# OurEDA-P1K_Network.net
KiCad netlist of a schematic drawn in Altium Designer
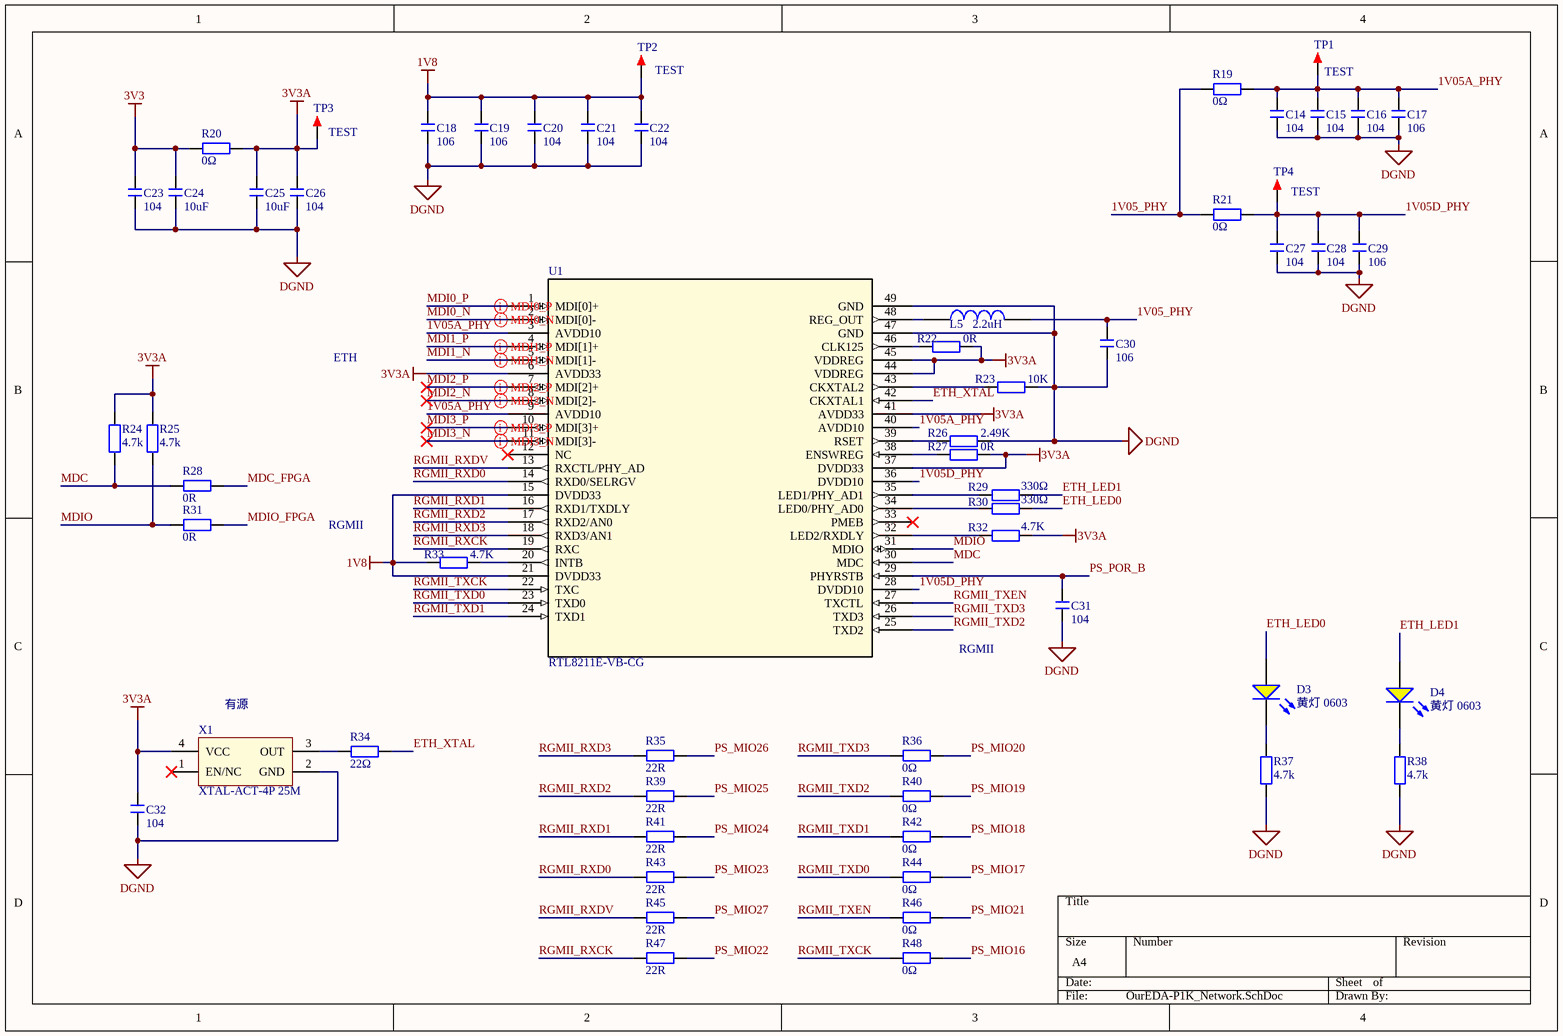
[diagram p0: OurEDA-P1K_Network.SchDoc]

(export (version "E")
  (design (tool "Eeschema 10.0.6"))
  (components
    (comp (ref "C14")
      (value "104")
      (footprint "C 0603_L")
      (description "无极性贴片电容")
      (fields (field (name "版权归属") "源创客"))
      (libsource (lib "3.1   - 电阻-电容-电感") (part "C"))
    )
    (comp (ref "C15")
      (value "104")
      (footprint "C 0603_L")
      (description "无极性贴片电容")
      (fields (field (name "版权归属") "源创客"))
      (libsource (lib "3.1   - 电阻-电容-电感") (part "C"))
    )
    (comp (ref "C16")
      (value "104")
      (footprint "C 0603_L")
      (description "无极性贴片电容")
      (fields (field (name "版权归属") "源创客"))
      (libsource (lib "3.1   - 电阻-电容-电感") (part "C"))
    )
    (comp (ref "C17")
      (value "106")
      (footprint "C 0603_L")
      (description "无极性贴片电容")
      (fields (field (name "版权归属") "源创客"))
      (libsource (lib "3.1   - 电阻-电容-电感") (part "C"))
    )
    (comp (ref "C18")
      (value "106")
      (footprint "C 0603_L")
      (description "无极性贴片电容")
      (fields (field (name "版权归属") "源创客"))
      (libsource (lib "3.1   - 电阻-电容-电感") (part "C"))
    )
    (comp (ref "C19")
      (value "106")
      (footprint "C 0603_L")
      (description "无极性贴片电容")
      (fields (field (name "版权归属") "源创客"))
      (libsource (lib "3.1   - 电阻-电容-电感") (part "C"))
    )
    (comp (ref "C20")
      (value "104")
      (footprint "C 0603_L")
      (description "无极性贴片电容")
      (fields (field (name "版权归属") "源创客"))
      (libsource (lib "3.1   - 电阻-电容-电感") (part "C"))
    )
    (comp (ref "C21")
      (value "104")
      (footprint "C 0603_L")
      (description "无极性贴片电容")
      (fields (field (name "版权归属") "源创客"))
      (libsource (lib "3.1   - 电阻-电容-电感") (part "C"))
    )
    (comp (ref "C22")
      (value "104")
      (footprint "C 0603_L")
      (description "无极性贴片电容")
      (fields (field (name "版权归属") "源创客"))
      (libsource (lib "3.1   - 电阻-电容-电感") (part "C"))
    )
    (comp (ref "C23")
      (value "104")
      (footprint "C 0603_L")
      (description "无极性贴片电容")
      (fields (field (name "版权归属") "源创客"))
      (libsource (lib "3.1   - 电阻-电容-电感") (part "C"))
    )
    (comp (ref "C24")
      (value "10uF")
      (footprint "C 0603_L")
      (description "无极性贴片电容")
      (fields (field (name "版权归属") "源创客"))
      (libsource (lib "3.1   - 电阻-电容-电感") (part "C"))
    )
    (comp (ref "C25")
      (value "10uF")
      (footprint "C 0603_L")
      (description "无极性贴片电容")
      (fields (field (name "版权归属") "源创客"))
      (libsource (lib "3.1   - 电阻-电容-电感") (part "C"))
    )
    (comp (ref "C26")
      (value "104")
      (footprint "C 0603_L")
      (description "无极性贴片电容")
      (fields (field (name "版权归属") "源创客"))
      (libsource (lib "3.1   - 电阻-电容-电感") (part "C"))
    )
    (comp (ref "C27")
      (value "104")
      (footprint "C 0603_L")
      (description "无极性贴片电容")
      (fields (field (name "版权归属") "源创客"))
      (libsource (lib "3.1   - 电阻-电容-电感") (part "C"))
    )
    (comp (ref "C28")
      (value "104")
      (footprint "C 0603_L")
      (description "无极性贴片电容")
      (fields (field (name "版权归属") "源创客"))
      (libsource (lib "3.1   - 电阻-电容-电感") (part "C"))
    )
    (comp (ref "C29")
      (value "106")
      (footprint "C 0603_L")
      (description "无极性贴片电容")
      (fields (field (name "版权归属") "源创客"))
      (libsource (lib "3.1   - 电阻-电容-电感") (part "C"))
    )
    (comp (ref "C30")
      (value "106")
      (footprint "C 0603_L")
      (description "无极性贴片电容")
      (fields (field (name "版权归属") "源创客"))
      (libsource (lib "3.1   - 电阻-电容-电感") (part "C"))
    )
    (comp (ref "C31")
      (value "104")
      (footprint "C 0603_L")
      (description "无极性贴片电容")
      (fields (field (name "版权归属") "源创客"))
      (libsource (lib "3.1   - 电阻-电容-电感") (part "C"))
    )
    (comp (ref "C32")
      (value "104")
      (footprint "C 0603_L")
      (description "无极性贴片电容")
      (fields (field (name "版权归属") "源创客"))
      (libsource (lib "3.1   - 电阻-电容-电感") (part "C"))
    )
    (comp (ref "D3")
      (value "黄灯 0603")
      (footprint "0603_LED_S1")
      (description "发光二极管")
      (libsource (lib "Miscellaneous Devices LC") (part "0603 黄灯"))
    )
    (comp (ref "D4")
      (value "黄灯 0603")
      (footprint "0603_LED_S1")
      (description "发光二极管")
      (libsource (lib "Miscellaneous Devices LC") (part "0603 黄灯"))
    )
    (comp (ref "L5")
      (value "2.2uH")
      (footprint "0805L")
      (description "INDUCTOR")
      (libsource (lib "电感") (part "INDUCTOR"))
    )
    (comp (ref "R19")
      (value "0Ω")
      (footprint "R 0603_L")
      (description "贴片电阻")
      (fields (field (name "版权归属") "源创客"))
      (libsource (lib "3.1   - 电阻-电容-电感") (part "R"))
    )
    (comp (ref "R20")
      (value "0Ω")
      (footprint "R 0805_L")
      (description "贴片电阻")
      (fields (field (name "版权归属") "源创客"))
      (libsource (lib "3.1   - 电阻-电容-电感") (part "R"))
    )
    (comp (ref "R21")
      (value "0Ω")
      (footprint "R 0603_L")
      (description "贴片电阻")
      (fields (field (name "版权归属") "源创客"))
      (libsource (lib "3.1   - 电阻-电容-电感") (part "R"))
    )
    (comp (ref "R22")
      (value "0R")
      (footprint "R 0603_L")
      (description "贴片电阻")
      (fields (field (name "版权归属") "源创客"))
      (libsource (lib "3.1   - 电阻-电容-电感") (part "R"))
    )
    (comp (ref "R23")
      (value "10K")
      (footprint "R 0603_L")
      (description "贴片电阻")
      (fields (field (name "版权归属") "源创客"))
      (libsource (lib "3.1   - 电阻-电容-电感") (part "R"))
    )
    (comp (ref "R24")
      (value "4.7k")
      (footprint "R 0603_L")
      (description "贴片电阻")
      (fields (field (name "版权归属") "源创客"))
      (libsource (lib "3.1   - 电阻-电容-电感") (part "R"))
    )
    (comp (ref "R25")
      (value "4.7k")
      (footprint "R 0603_L")
      (description "贴片电阻")
      (fields (field (name "版权归属") "源创客"))
      (libsource (lib "3.1   - 电阻-电容-电感") (part "R"))
    )
    (comp (ref "R26")
      (value "2.49K")
      (footprint "R 0603_L")
      (description "贴片电阻")
      (fields (field (name "版权归属") "源创客"))
      (libsource (lib "3.1   - 电阻-电容-电感") (part "R"))
    )
    (comp (ref "R27")
      (value "0R")
      (footprint "R 0603_L")
      (description "贴片电阻")
      (fields (field (name "版权归属") "源创客"))
      (libsource (lib "3.1   - 电阻-电容-电感") (part "R"))
    )
    (comp (ref "R28")
      (value "0R")
      (footprint "R 0603_L")
      (description "贴片电阻")
      (fields (field (name "版权归属") "源创客"))
      (libsource (lib "3.1   - 电阻-电容-电感") (part "R"))
    )
    (comp (ref "R29")
      (value "330Ω")
      (footprint "R 0603_L")
      (description "贴片电阻")
      (fields (field (name "版权归属") "源创客"))
      (libsource (lib "3.1   - 电阻-电容-电感") (part "R"))
    )
    (comp (ref "R30")
      (value "330Ω")
      (footprint "R 0603_L")
      (description "贴片电阻")
      (fields (field (name "版权归属") "源创客"))
      (libsource (lib "3.1   - 电阻-电容-电感") (part "R"))
    )
    (comp (ref "R31")
      (value "0R")
      (footprint "R 0603_L")
      (description "贴片电阻")
      (fields (field (name "版权归属") "源创客"))
      (libsource (lib "3.1   - 电阻-电容-电感") (part "R"))
    )
    (comp (ref "R32")
      (value "4.7K")
      (footprint "R 0603_L")
      (description "贴片电阻")
      (fields (field (name "版权归属") "源创客"))
      (libsource (lib "3.1   - 电阻-电容-电感") (part "R"))
    )
    (comp (ref "R33")
      (value "4.7K")
      (footprint "R 0603_L")
      (description "贴片电阻")
      (fields (field (name "版权归属") "源创客"))
      (libsource (lib "3.1   - 电阻-电容-电感") (part "R"))
    )
    (comp (ref "R34")
      (value "22Ω")
      (footprint "R 0603_L")
      (description "贴片电阻")
      (fields (field (name "版权归属") "源创客"))
      (libsource (lib "3.1   - 电阻-电容-电感") (part "R"))
    )
    (comp (ref "R35")
      (value "22R")
      (footprint "R 0603_L")
      (description "贴片电阻")
      (fields (field (name "版权归属") "源创客"))
      (libsource (lib "3.1   - 电阻-电容-电感") (part "R"))
    )
    (comp (ref "R36")
      (value "0Ω")
      (footprint "R 0603_L")
      (description "贴片电阻")
      (fields (field (name "版权归属") "源创客"))
      (libsource (lib "3.1   - 电阻-电容-电感") (part "R"))
    )
    (comp (ref "R37")
      (value "4.7k")
      (footprint "R 0603_L")
      (description "贴片电阻")
      (fields (field (name "版权归属") "源创客"))
      (libsource (lib "3.1   - 电阻-电容-电感") (part "R"))
    )
    (comp (ref "R38")
      (value "4.7k")
      (footprint "R 0603_L")
      (description "贴片电阻")
      (fields (field (name "版权归属") "源创客"))
      (libsource (lib "3.1   - 电阻-电容-电感") (part "R"))
    )
    (comp (ref "R39")
      (value "22R")
      (footprint "R 0603_L")
      (description "贴片电阻")
      (fields (field (name "版权归属") "源创客"))
      (libsource (lib "3.1   - 电阻-电容-电感") (part "R"))
    )
    (comp (ref "R40")
      (value "0Ω")
      (footprint "R 0603_L")
      (description "贴片电阻")
      (fields (field (name "版权归属") "源创客"))
      (libsource (lib "3.1   - 电阻-电容-电感") (part "R"))
    )
    (comp (ref "R41")
      (value "22R")
      (footprint "R 0603_L")
      (description "贴片电阻")
      (fields (field (name "版权归属") "源创客"))
      (libsource (lib "3.1   - 电阻-电容-电感") (part "R"))
    )
    (comp (ref "R42")
      (value "0Ω")
      (footprint "R 0603_L")
      (description "贴片电阻")
      (fields (field (name "版权归属") "源创客"))
      (libsource (lib "3.1   - 电阻-电容-电感") (part "R"))
    )
    (comp (ref "R43")
      (value "22R")
      (footprint "R 0603_L")
      (description "贴片电阻")
      (fields (field (name "版权归属") "源创客"))
      (libsource (lib "3.1   - 电阻-电容-电感") (part "R"))
    )
    (comp (ref "R44")
      (value "0Ω")
      (footprint "R 0603_L")
      (description "贴片电阻")
      (fields (field (name "版权归属") "源创客"))
      (libsource (lib "3.1   - 电阻-电容-电感") (part "R"))
    )
    (comp (ref "R45")
      (value "22R")
      (footprint "R 0603_L")
      (description "贴片电阻")
      (fields (field (name "版权归属") "源创客"))
      (libsource (lib "3.1   - 电阻-电容-电感") (part "R"))
    )
    (comp (ref "R46")
      (value "0Ω")
      (footprint "R 0603_L")
      (description "贴片电阻")
      (fields (field (name "版权归属") "源创客"))
      (libsource (lib "3.1   - 电阻-电容-电感") (part "R"))
    )
    (comp (ref "R47")
      (value "22R")
      (footprint "R 0603_L")
      (description "贴片电阻")
      (fields (field (name "版权归属") "源创客"))
      (libsource (lib "3.1   - 电阻-电容-电感") (part "R"))
    )
    (comp (ref "R48")
      (value "0Ω")
      (footprint "R 0603_L")
      (description "贴片电阻")
      (fields (field (name "版权归属") "源创客"))
      (libsource (lib "3.1   - 电阻-电容-电感") (part "R"))
    )
    (comp (ref "TP1")
      (value "TEST")
      (footprint "TEST 1")
      (description "测试点")
      (fields (field (name "版权归属") "源创客"))
      (libsource (lib "15.1 - 未分类器件") (part "TEST"))
    )
    (comp (ref "TP2")
      (value "TEST")
      (footprint "TEST 1")
      (description "测试点")
      (fields (field (name "版权归属") "源创客"))
      (libsource (lib "15.1 - 未分类器件") (part "TEST"))
    )
    (comp (ref "TP3")
      (value "TEST")
      (footprint "TEST 1")
      (description "测试点")
      (fields (field (name "版权归属") "源创客"))
      (libsource (lib "15.1 - 未分类器件") (part "TEST"))
    )
    (comp (ref "TP4")
      (value "TEST")
      (footprint "TEST 1")
      (description "测试点")
      (fields (field (name "版权归属") "源创客"))
      (libsource (lib "15.1 - 未分类器件") (part "TEST"))
    )
    (comp (ref "U1")
      (value "RTL8211E-VB-CG")
      (footprint "QFN48 6X6")
      (description "No Description Available")
      (fields (field (name "COPYRIGHT") "Copyright (C) 2022 Ultra Librarian. All rights reserved."))
      (libsource (lib "MySchLib") (part "RTL8211E-VB-CG"))
    )
    (comp (ref "X1")
      (value "XTAL-ACT-4P 25M")
      (footprint "OSC 1612-4P")
      (description "4脚有源晶振")
      (libsource (lib "晶振") (part "XTAL-ACT-4P"))
    )
  )
  (nets
    (net (code "1") (name "/1V05A_PHY") (class "Default")
      (node (ref "C14") (pin "2") (pinfunction "2_2") (pintype "passive"))
      (node (ref "C15") (pin "2") (pinfunction "2_2") (pintype "passive"))
      (node (ref "C16") (pin "2") (pinfunction "2_2") (pintype "passive"))
      (node (ref "C17") (pin "2") (pinfunction "2_2") (pintype "passive"))
      (node (ref "R19") (pin "2") (pinfunction "2_2") (pintype "passive"))
      (node (ref "TP1") (pin "1") (pinfunction "1_1") (pintype "passive"))
      (node (ref "U1") (pin "3") (pinfunction "AVDD10_3") (pintype "power_in"))
      (node (ref "U1") (pin "40") (pinfunction "AVDD10_40") (pintype "power_in"))
      (node (ref "U1") (pin "9") (pinfunction "AVDD10_9") (pintype "power_in"))
    )
    (net (code "2") (name "/1V05D_PHY") (class "Default")
      (node (ref "C27") (pin "2") (pinfunction "2_2") (pintype "passive"))
      (node (ref "C28") (pin "2") (pinfunction "2_2") (pintype "passive"))
      (node (ref "C29") (pin "2") (pinfunction "2_2") (pintype "passive"))
      (node (ref "R21") (pin "2") (pinfunction "2_2") (pintype "passive"))
      (node (ref "TP4") (pin "1") (pinfunction "1_1") (pintype "passive"))
      (node (ref "U1") (pin "28") (pinfunction "DVDD10_28") (pintype "power_in"))
      (node (ref "U1") (pin "36") (pinfunction "DVDD10_36") (pintype "power_in"))
    )
    (net (code "3") (name "/1V05_PHY") (class "Default")
      (node (ref "C30") (pin "1") (pinfunction "1_1") (pintype "passive"))
      (node (ref "L5") (pin "2") (pinfunction "2_2") (pintype "passive"))
      (node (ref "R19") (pin "1") (pinfunction "1_1") (pintype "passive"))
      (node (ref "R21") (pin "1") (pinfunction "1_1") (pintype "passive"))
    )
    (net (code "4") (name "/ETH_LED0") (class "Default")
      (node (ref "D3") (pin "A") (pinfunction "A_A") (pintype "passive"))
      (node (ref "R30") (pin "1") (pinfunction "1_1") (pintype "passive"))
    )
    (net (code "5") (name "/ETH_LED1") (class "Default")
      (node (ref "D4") (pin "A") (pinfunction "A_A") (pintype "passive"))
      (node (ref "R29") (pin "1") (pinfunction "1_1") (pintype "passive"))
    )
    (net (code "6") (name "/ETH_XTAL") (class "Default")
      (node (ref "R34") (pin "2") (pinfunction "2_2") (pintype "passive"))
      (node (ref "U1") (pin "42") (pinfunction "CKXTAL1_42") (pintype "input"))
    )
    (net (code "7") (name "/MDC") (class "Default")
      (node (ref "R24") (pin "2") (pinfunction "2_2") (pintype "passive"))
      (node (ref "R28") (pin "2") (pinfunction "2_2") (pintype "passive"))
      (node (ref "U1") (pin "30") (pinfunction "MDC_30") (pintype "input"))
    )
    (net (code "8") (name "/MDC_FPGA") (class "Default")
      (node (ref "R28") (pin "1") (pinfunction "1_1") (pintype "passive"))
    )
    (net (code "9") (name "/MDI0_N") (class "Default")
      (node (ref "U1") (pin "2") (pinfunction "MDI[0]-_2") (pintype "bidirectional"))
    )
    (net (code "10") (name "/MDI0_P") (class "Default")
      (node (ref "U1") (pin "1") (pinfunction "MDI[0]+_1") (pintype "bidirectional"))
    )
    (net (code "11") (name "/MDI1_N") (class "Default")
      (node (ref "U1") (pin "5") (pinfunction "MDI[1]-_5") (pintype "bidirectional"))
    )
    (net (code "12") (name "/MDI1_P") (class "Default")
      (node (ref "U1") (pin "4") (pinfunction "MDI[1]+_4") (pintype "bidirectional"))
    )
    (net (code "13") (name "/MDI2_N") (class "Default")
      (node (ref "U1") (pin "8") (pinfunction "MDI[2]-_8") (pintype "bidirectional+no_connect"))
    )
    (net (code "14") (name "/MDI2_P") (class "Default")
      (node (ref "U1") (pin "7") (pinfunction "MDI[2]+_7") (pintype "bidirectional+no_connect"))
    )
    (net (code "15") (name "/MDI3_N") (class "Default")
      (node (ref "U1") (pin "11") (pinfunction "MDI[3]-_11") (pintype "bidirectional+no_connect"))
    )
    (net (code "16") (name "/MDI3_P") (class "Default")
      (node (ref "U1") (pin "10") (pinfunction "MDI[3]+_10") (pintype "bidirectional+no_connect"))
    )
    (net (code "17") (name "/MDIO") (class "Default")
      (node (ref "R25") (pin "2") (pinfunction "2_2") (pintype "passive"))
      (node (ref "R31") (pin "2") (pinfunction "2_2") (pintype "passive"))
      (node (ref "U1") (pin "31") (pinfunction "MDIO_31") (pintype "bidirectional"))
    )
    (net (code "18") (name "/MDIO_FPGA") (class "Default")
      (node (ref "R31") (pin "1") (pinfunction "1_1") (pintype "passive"))
    )
    (net (code "19") (name "/PS_MIO16") (class "Default")
      (node (ref "R48") (pin "2") (pinfunction "2_2") (pintype "passive"))
    )
    (net (code "20") (name "/PS_MIO17") (class "Default")
      (node (ref "R44") (pin "2") (pinfunction "2_2") (pintype "passive"))
    )
    (net (code "21") (name "/PS_MIO18") (class "Default")
      (node (ref "R42") (pin "2") (pinfunction "2_2") (pintype "passive"))
    )
    (net (code "22") (name "/PS_MIO19") (class "Default")
      (node (ref "R40") (pin "2") (pinfunction "2_2") (pintype "passive"))
    )
    (net (code "23") (name "/PS_MIO20") (class "Default")
      (node (ref "R36") (pin "2") (pinfunction "2_2") (pintype "passive"))
    )
    (net (code "24") (name "/PS_MIO21") (class "Default")
      (node (ref "R46") (pin "2") (pinfunction "2_2") (pintype "passive"))
    )
    (net (code "25") (name "/PS_MIO22") (class "Default")
      (node (ref "R47") (pin "2") (pinfunction "2_2") (pintype "passive"))
    )
    (net (code "26") (name "/PS_MIO23") (class "Default")
      (node (ref "R43") (pin "2") (pinfunction "2_2") (pintype "passive"))
    )
    (net (code "27") (name "/PS_MIO24") (class "Default")
      (node (ref "R41") (pin "2") (pinfunction "2_2") (pintype "passive"))
    )
    (net (code "28") (name "/PS_MIO25") (class "Default")
      (node (ref "R39") (pin "2") (pinfunction "2_2") (pintype "passive"))
    )
    (net (code "29") (name "/PS_MIO26") (class "Default")
      (node (ref "R35") (pin "2") (pinfunction "2_2") (pintype "passive"))
    )
    (net (code "30") (name "/PS_MIO27") (class "Default")
      (node (ref "R45") (pin "2") (pinfunction "2_2") (pintype "passive"))
    )
    (net (code "31") (name "/PS_POR_B") (class "Default")
      (node (ref "C31") (pin "1") (pinfunction "1_1") (pintype "passive"))
      (node (ref "U1") (pin "29") (pinfunction "PHYRSTB_29") (pintype "input"))
    )
    (net (code "32") (name "/RGMII_RXCK") (class "Default")
      (node (ref "R47") (pin "1") (pinfunction "1_1") (pintype "passive"))
      (node (ref "U1") (pin "19") (pinfunction "RXC_19") (pintype "output"))
    )
    (net (code "33") (name "/RGMII_RXD0") (class "Default")
      (node (ref "R43") (pin "1") (pinfunction "1_1") (pintype "passive"))
      (node (ref "U1") (pin "14") (pinfunction "RXD0/SELRGV_14") (pintype "output"))
    )
    (net (code "34") (name "/RGMII_RXD1") (class "Default")
      (node (ref "R41") (pin "1") (pinfunction "1_1") (pintype "passive"))
      (node (ref "U1") (pin "16") (pinfunction "RXD1/TXDLY_16") (pintype "output"))
    )
    (net (code "35") (name "/RGMII_RXD2") (class "Default")
      (node (ref "R39") (pin "1") (pinfunction "1_1") (pintype "passive"))
      (node (ref "U1") (pin "17") (pinfunction "RXD2/AN0_17") (pintype "output"))
    )
    (net (code "36") (name "/RGMII_RXD3") (class "Default")
      (node (ref "R35") (pin "1") (pinfunction "1_1") (pintype "passive"))
      (node (ref "U1") (pin "18") (pinfunction "RXD3/AN1_18") (pintype "output"))
    )
    (net (code "37") (name "/RGMII_RXDV") (class "Default")
      (node (ref "R45") (pin "1") (pinfunction "1_1") (pintype "passive"))
      (node (ref "U1") (pin "13") (pinfunction "RXCTL/PHY_AD_13") (pintype "output"))
    )
    (net (code "38") (name "/RGMII_TXCK") (class "Default")
      (node (ref "R48") (pin "1") (pinfunction "1_1") (pintype "passive"))
      (node (ref "U1") (pin "22") (pinfunction "TXC_22") (pintype "input"))
    )
    (net (code "39") (name "/RGMII_TXD0") (class "Default")
      (node (ref "R44") (pin "1") (pinfunction "1_1") (pintype "passive"))
      (node (ref "U1") (pin "23") (pinfunction "TXD0_23") (pintype "input"))
    )
    (net (code "40") (name "/RGMII_TXD1") (class "Default")
      (node (ref "R42") (pin "1") (pinfunction "1_1") (pintype "passive"))
      (node (ref "U1") (pin "24") (pinfunction "TXD1_24") (pintype "input"))
    )
    (net (code "41") (name "/RGMII_TXD2") (class "Default")
      (node (ref "R40") (pin "1") (pinfunction "1_1") (pintype "passive"))
      (node (ref "U1") (pin "25") (pinfunction "TXD2_25") (pintype "input"))
    )
    (net (code "42") (name "/RGMII_TXD3") (class "Default")
      (node (ref "R36") (pin "1") (pinfunction "1_1") (pintype "passive"))
      (node (ref "U1") (pin "26") (pinfunction "TXD3_26") (pintype "input"))
    )
    (net (code "43") (name "/RGMII_TXEN") (class "Default")
      (node (ref "R46") (pin "1") (pinfunction "1_1") (pintype "passive"))
      (node (ref "U1") (pin "27") (pinfunction "TXCTL_27") (pintype "input"))
    )
    (net (code "44") (name "1V8") (class "Default")
      (node (ref "C18") (pin "2") (pinfunction "2_2") (pintype "passive"))
      (node (ref "C19") (pin "2") (pinfunction "2_2") (pintype "passive"))
      (node (ref "C20") (pin "2") (pinfunction "2_2") (pintype "passive"))
      (node (ref "C21") (pin "2") (pinfunction "2_2") (pintype "passive"))
      (node (ref "C22") (pin "2") (pinfunction "2_2") (pintype "passive"))
      (node (ref "R33") (pin "2") (pinfunction "2_2") (pintype "passive"))
      (node (ref "TP2") (pin "1") (pinfunction "1_1") (pintype "passive"))
      (node (ref "U1") (pin "15") (pinfunction "DVDD33_15") (pintype "power_in"))
      (node (ref "U1") (pin "21") (pinfunction "DVDD33_21") (pintype "power_in"))
    )
    (net (code "45") (name "3V3") (class "Default")
      (node (ref "C23") (pin "2") (pinfunction "2_2") (pintype "passive"))
      (node (ref "C24") (pin "2") (pinfunction "2_2") (pintype "passive"))
      (node (ref "R20") (pin "1") (pinfunction "1_1") (pintype "passive"))
    )
    (net (code "46") (name "3V3A") (class "Default")
      (node (ref "C25") (pin "2") (pinfunction "2_2") (pintype "passive"))
      (node (ref "C26") (pin "2") (pinfunction "2_2") (pintype "passive"))
      (node (ref "C32") (pin "2") (pinfunction "2_2") (pintype "passive"))
      (node (ref "R20") (pin "2") (pinfunction "2_2") (pintype "passive"))
      (node (ref "R22") (pin "1") (pinfunction "1_1") (pintype "passive"))
      (node (ref "R24") (pin "1") (pinfunction "1_1") (pintype "passive"))
      (node (ref "R25") (pin "1") (pinfunction "1_1") (pintype "passive"))
      (node (ref "R27") (pin "1") (pinfunction "1_1") (pintype "passive"))
      (node (ref "R32") (pin "1") (pinfunction "1_1") (pintype "passive"))
      (node (ref "TP3") (pin "1") (pinfunction "1_1") (pintype "passive"))
      (node (ref "U1") (pin "37") (pinfunction "DVDD33_37") (pintype "power_in"))
      (node (ref "U1") (pin "41") (pinfunction "AVDD33_41") (pintype "power_in"))
      (node (ref "U1") (pin "44") (pinfunction "VDDREG_44") (pintype "power_in"))
      (node (ref "U1") (pin "45") (pinfunction "VDDREG_45") (pintype "power_in"))
      (node (ref "U1") (pin "6") (pinfunction "AVDD33_6") (pintype "power_in"))
      (node (ref "X1") (pin "4") (pinfunction "VCC_4") (pintype "passive"))
    )
    (net (code "47") (name "DGND") (class "Default")
      (node (ref "C14") (pin "1") (pinfunction "1_1") (pintype "passive"))
      (node (ref "C15") (pin "1") (pinfunction "1_1") (pintype "passive"))
      (node (ref "C16") (pin "1") (pinfunction "1_1") (pintype "passive"))
      (node (ref "C17") (pin "1") (pinfunction "1_1") (pintype "passive"))
      (node (ref "C18") (pin "1") (pinfunction "1_1") (pintype "passive"))
      (node (ref "C19") (pin "1") (pinfunction "1_1") (pintype "passive"))
      (node (ref "C20") (pin "1") (pinfunction "1_1") (pintype "passive"))
      (node (ref "C21") (pin "1") (pinfunction "1_1") (pintype "passive"))
      (node (ref "C22") (pin "1") (pinfunction "1_1") (pintype "passive"))
      (node (ref "C23") (pin "1") (pinfunction "1_1") (pintype "passive"))
      (node (ref "C24") (pin "1") (pinfunction "1_1") (pintype "passive"))
      (node (ref "C25") (pin "1") (pinfunction "1_1") (pintype "passive"))
      (node (ref "C26") (pin "1") (pinfunction "1_1") (pintype "passive"))
      (node (ref "C27") (pin "1") (pinfunction "1_1") (pintype "passive"))
      (node (ref "C28") (pin "1") (pinfunction "1_1") (pintype "passive"))
      (node (ref "C29") (pin "1") (pinfunction "1_1") (pintype "passive"))
      (node (ref "C30") (pin "2") (pinfunction "2_2") (pintype "passive"))
      (node (ref "C31") (pin "2") (pinfunction "2_2") (pintype "passive"))
      (node (ref "C32") (pin "1") (pinfunction "1_1") (pintype "passive"))
      (node (ref "R23") (pin "1") (pinfunction "1_1") (pintype "passive"))
      (node (ref "R26") (pin "1") (pinfunction "1_1") (pintype "passive"))
      (node (ref "R37") (pin "1") (pinfunction "1_1") (pintype "passive"))
      (node (ref "R38") (pin "1") (pinfunction "1_1") (pintype "passive"))
      (node (ref "U1") (pin "47") (pinfunction "GND_47") (pintype "passive"))
      (node (ref "U1") (pin "49") (pinfunction "GND_49") (pintype "passive"))
      (node (ref "X1") (pin "2") (pinfunction "GND_2") (pintype "passive"))
    )
    (net (code "48") (name "Net-(D3-PadK)") (class "Default")
      (node (ref "D3") (pin "K") (pinfunction "K_K") (pintype "passive"))
      (node (ref "R37") (pin "2") (pinfunction "2_2") (pintype "passive"))
    )
    (net (code "49") (name "Net-(D4-PadK)") (class "Default")
      (node (ref "D4") (pin "K") (pinfunction "K_K") (pintype "passive"))
      (node (ref "R38") (pin "2") (pinfunction "2_2") (pintype "passive"))
    )
    (net (code "50") (name "Net-(U1-CKXTAL2)") (class "Default")
      (node (ref "R23") (pin "2") (pinfunction "2_2") (pintype "passive"))
      (node (ref "U1") (pin "43") (pinfunction "CKXTAL2_43") (pintype "output"))
    )
    (net (code "51") (name "Net-(U1-CLK125)") (class "Default")
      (node (ref "R22") (pin "2") (pinfunction "2_2") (pintype "passive"))
      (node (ref "U1") (pin "46") (pinfunction "CLK125_46") (pintype "output"))
    )
    (net (code "52") (name "Net-(U1-ENSWREG)") (class "Default")
      (node (ref "R27") (pin "2") (pinfunction "2_2") (pintype "passive"))
      (node (ref "U1") (pin "38") (pinfunction "ENSWREG_38") (pintype "input"))
    )
    (net (code "53") (name "Net-(U1-INTB)") (class "Default")
      (node (ref "R33") (pin "1") (pinfunction "1_1") (pintype "passive"))
      (node (ref "U1") (pin "20") (pinfunction "INTB_20") (pintype "output"))
    )
    (net (code "54") (name "Net-(U1-LED0{slash}PHY_AD0)") (class "Default")
      (node (ref "R30") (pin "2") (pinfunction "2_2") (pintype "passive"))
      (node (ref "U1") (pin "34") (pinfunction "LED0/PHY_AD0_34") (pintype "output"))
    )
    (net (code "55") (name "Net-(U1-LED1{slash}PHY_AD1)") (class "Default")
      (node (ref "R29") (pin "2") (pinfunction "2_2") (pintype "passive"))
      (node (ref "U1") (pin "35") (pinfunction "LED1/PHY_AD1_35") (pintype "output"))
    )
    (net (code "56") (name "Net-(U1-LED2{slash}RXDLY)") (class "Default")
      (node (ref "R32") (pin "2") (pinfunction "2_2") (pintype "passive"))
      (node (ref "U1") (pin "32") (pinfunction "LED2/RXDLY_32") (pintype "output"))
    )
    (net (code "57") (name "Net-(U1-REG_OUT)") (class "Default")
      (node (ref "L5") (pin "1") (pinfunction "1_1") (pintype "passive"))
      (node (ref "U1") (pin "48") (pinfunction "REG_OUT_48") (pintype "output"))
    )
    (net (code "58") (name "Net-(U1-RSET)") (class "Default")
      (node (ref "R26") (pin "2") (pinfunction "2_2") (pintype "passive"))
      (node (ref "U1") (pin "39") (pinfunction "RSET_39") (pintype "output"))
    )
    (net (code "59") (name "Net-(X1-OUT)") (class "Default")
      (node (ref "R34") (pin "1") (pinfunction "1_1") (pintype "passive"))
      (node (ref "X1") (pin "3") (pinfunction "OUT_3") (pintype "passive"))
    )
    (net (code "60") (name "unconnected-(U1-NC-Pad12)") (class "Default")
      (node (ref "U1") (pin "12") (pinfunction "NC_12") (pintype "passive+no_connect"))
    )
    (net (code "61") (name "unconnected-(U1-PMEB-Pad33)") (class "Default")
      (node (ref "U1") (pin "33") (pinfunction "PMEB_33") (pintype "output+no_connect"))
    )
    (net (code "62") (name "unconnected-(X1-EN{slash}NC-Pad1)") (class "Default")
      (node (ref "X1") (pin "1") (pinfunction "EN/NC_1") (pintype "passive+no_connect"))
    )
  )
)
